# irf540_V2_0.net
KiCad netlist of a schematic drawn in Altium Designer
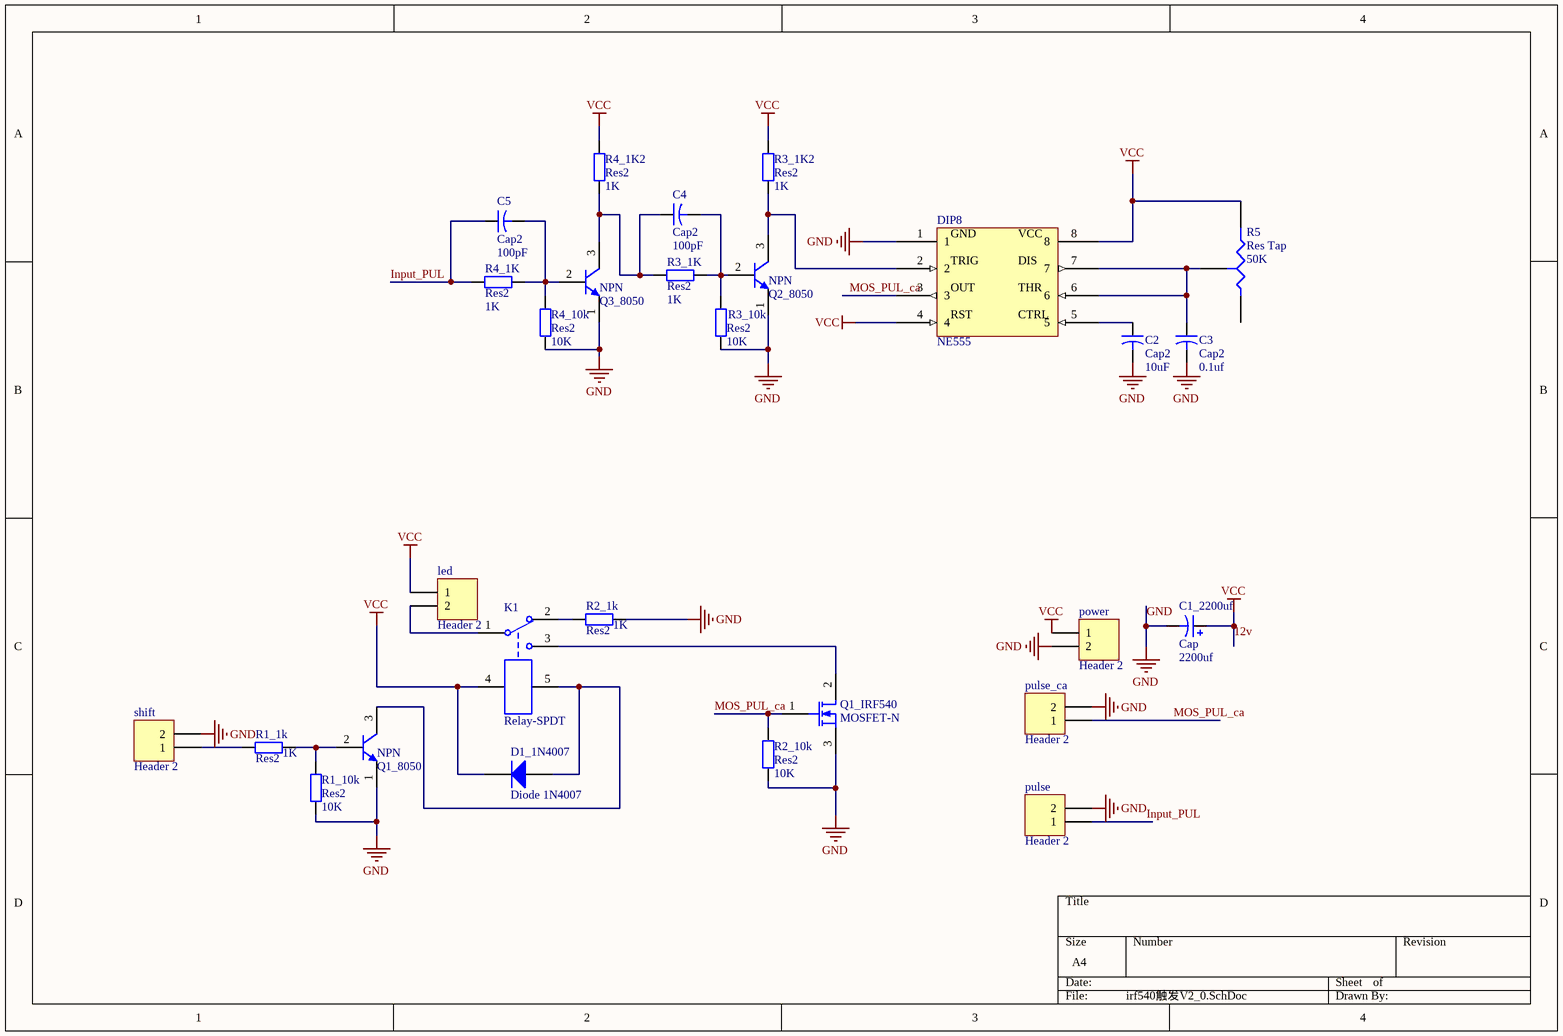
[diagram p0: irf540触发V2_0.SchDoc]

(export (version "E")
  (design (tool "Eeschema 10.0.6"))
  (components
    (comp (ref "C1_2200uf")
      (value "Cap")
      (footprint "RB7.6-15")
      (description "Polarized Capacitor (Radial)")
      (fields (field (name "ALTIUM_VALUE") "2200uf") (field (name "PUBLISHER") "Altium Limited"))
      (libsource (lib "Miscellaneous Devices") (part "Cap Pol1"))
    )
    (comp (ref "C2")
      (value "Cap2")
      (footprint "CAPR5-4X5")
      (description "Capacitor")
      (fields (field (name "ALTIUM_VALUE") "10uF") (field (name "PUBLISHER") "Altium Limited"))
      (libsource (lib "Miscellaneous Devices") (part "Cap2"))
    )
    (comp (ref "C3")
      (value "Cap2")
      (footprint "CAPR5-4X5")
      (description "Capacitor")
      (fields (field (name "ALTIUM_VALUE") "0.1uf") (field (name "PUBLISHER") "Altium Limited"))
      (libsource (lib "Miscellaneous Devices") (part "Cap2"))
    )
    (comp (ref "C4")
      (value "Cap2")
      (footprint "CAPR5-4X5")
      (description "Capacitor")
      (fields (field (name "ALTIUM_VALUE") "100pF") (field (name "PUBLISHER") "Altium Limited"))
      (libsource (lib "Miscellaneous Devices") (part "Cap2"))
    )
    (comp (ref "C5")
      (value "Cap2")
      (footprint "CAPR5-4X5")
      (description "Capacitor")
      (fields (field (name "ALTIUM_VALUE") "100pF") (field (name "PUBLISHER") "Altium Limited"))
      (libsource (lib "Miscellaneous Devices") (part "Cap2"))
    )
    (comp (ref "D1_1N4007")
      (value "Diode 1N4007")
      (footprint "DO-41")
      (description "1 Amp General Purpose Rectifier")
      (fields (field (name "PUBLISHER") "Altium Limited"))
      (libsource (lib "Miscellaneous Devices") (part "Diode 1N4007"))
    )
    (comp (ref "DIP8") (value "NE555") (footprint "DIP8") (libsource (lib "NE555") (part "NE555")))
    (comp (ref "K1")
      (value "Relay-SPDT")
      (footprint "RELAY_SDR")
      (description "Single-Pole Dual-Throw Relay")
      (fields (field (name "PUBLISHER") "Altium Limited"))
      (libsource (lib "Miscellaneous Devices") (part "Relay-SPDT"))
    )
    (comp (ref "led")
      (value "Header 2")
      (footprint "HDR1X2")
      (description "Header, 2-Pin")
      (fields (field (name "PUBLISHER") "Altium Limited"))
      (libsource (lib "") (part "Header 2_1"))
    )
    (comp (ref "power")
      (value "Header 2")
      (footprint "HDR1X2")
      (description "Header, 2-Pin")
      (fields (field (name "PUBLISHER") "Altium Limited"))
      (libsource (lib "") (part "Header 2_1"))
    )
    (comp (ref "pulse")
      (value "Header 2")
      (footprint "HDR1X2")
      (description "Header, 2-Pin")
      (fields (field (name "PUBLISHER") "Altium Limited"))
      (libsource (lib "Miscellaneous Connectors") (part "Header 2"))
    )
    (comp (ref "pulse_ca")
      (value "Header 2")
      (footprint "HDR1X2")
      (description "Header, 2-Pin")
      (fields (field (name "PUBLISHER") "Altium Limited"))
      (libsource (lib "Miscellaneous Connectors") (part "Header 2"))
    )
    (comp (ref "Q1_8050")
      (value "NPN")
      (footprint "TO-226-AA")
      (description "NPN Bipolar Transistor")
      (fields (field (name "PUBLISHER") "Altium Limited"))
      (libsource (lib "Miscellaneous Devices") (part "NPN"))
    )
    (comp (ref "Q1_IRF540")
      (value "MOSFET-N")
      (footprint "PCBComponent_1")
      (description "N-Channel MOSFET")
      (fields (field (name "PUBLISHER") "Altium Limited"))
      (libsource (lib "Miscellaneous Devices") (part "MOSFET-N"))
    )
    (comp (ref "Q2_8050")
      (value "NPN")
      (footprint "TO-226-AA")
      (description "NPN Bipolar Transistor")
      (fields (field (name "PUBLISHER") "Altium Limited"))
      (libsource (lib "Miscellaneous Devices") (part "NPN"))
    )
    (comp (ref "Q3_8050")
      (value "NPN")
      (footprint "TO-226-AA")
      (description "NPN Bipolar Transistor")
      (fields (field (name "PUBLISHER") "Altium Limited"))
      (libsource (lib "Miscellaneous Devices") (part "NPN"))
    )
    (comp (ref "R1_1k")
      (value "Res2")
      (footprint "AXIAL-0.4")
      (description "Resistor")
      (fields (field (name "ALTIUM_VALUE") "1K") (field (name "PUBLISHER") "Altium Limited"))
      (libsource (lib "") (part "Res2_3"))
    )
    (comp (ref "R1_10k")
      (value "Res2")
      (footprint "AXIAL-0.4")
      (description "Resistor")
      (fields (field (name "ALTIUM_VALUE") "10K") (field (name "PUBLISHER") "Altium Limited"))
      (libsource (lib "") (part "Res2_1"))
    )
    (comp (ref "R2_1k")
      (value "Res2")
      (footprint "AXIAL-0.4")
      (description "Resistor")
      (fields (field (name "ALTIUM_VALUE") "1K") (field (name "PUBLISHER") "Altium Limited"))
      (libsource (lib "") (part "Res2_3"))
    )
    (comp (ref "R2_10k")
      (value "Res2")
      (footprint "AXIAL-0.4")
      (description "Resistor")
      (fields (field (name "ALTIUM_VALUE") "10K") (field (name "PUBLISHER") "Altium Limited"))
      (libsource (lib "") (part "Res2_1"))
    )
    (comp (ref "R3_1K")
      (value "Res2")
      (footprint "AXIAL-0.4")
      (description "Resistor")
      (fields (field (name "ALTIUM_VALUE") "1K") (field (name "PUBLISHER") "Altium Limited"))
      (libsource (lib "Miscellaneous Devices") (part "Res2"))
    )
    (comp (ref "R3_1K2")
      (value "Res2")
      (footprint "AXIAL-0.4")
      (description "Resistor")
      (fields (field (name "ALTIUM_VALUE") "1K") (field (name "PUBLISHER") "Altium Limited"))
      (libsource (lib "") (part "Res2_2"))
    )
    (comp (ref "R3_10k")
      (value "Res2")
      (footprint "AXIAL-0.4")
      (description "Resistor")
      (fields (field (name "ALTIUM_VALUE") "10K") (field (name "PUBLISHER") "Altium Limited"))
      (libsource (lib "") (part "Res2_1"))
    )
    (comp (ref "R4_1K")
      (value "Res2")
      (footprint "AXIAL-0.4")
      (description "Resistor")
      (fields (field (name "ALTIUM_VALUE") "1K") (field (name "PUBLISHER") "Altium Limited"))
      (libsource (lib "Miscellaneous Devices") (part "Res2"))
    )
    (comp (ref "R4_1K2")
      (value "Res2")
      (footprint "AXIAL-0.4")
      (description "Resistor")
      (fields (field (name "ALTIUM_VALUE") "1K") (field (name "PUBLISHER") "Altium Limited"))
      (libsource (lib "") (part "Res2_2"))
    )
    (comp (ref "R4_10k")
      (value "Res2")
      (footprint "AXIAL-0.4")
      (description "Resistor")
      (fields (field (name "ALTIUM_VALUE") "10K") (field (name "PUBLISHER") "Altium Limited"))
      (libsource (lib "") (part "Res2_1"))
    )
    (comp (ref "R5")
      (value "Res Tap")
      (footprint "VR5")
      (description "Tapped Resistor")
      (fields (field (name "ALTIUM_VALUE") "50K") (field (name "PUBLISHER") "Altium Limited"))
      (libsource (lib "Miscellaneous Devices") (part "Res Tap"))
    )
    (comp (ref "shift")
      (value "Header 2")
      (footprint "HDR1X2")
      (description "Header, 2-Pin")
      (fields (field (name "PUBLISHER") "Altium Limited"))
      (libsource (lib "Miscellaneous Connectors") (part "Header 2"))
    )
  )
  (nets
    (net (code "1") (name "/Input_PUL") (class "Default")
      (node (ref "C5") (pin "1") (pinfunction "1_1") (pintype "passive"))
      (node (ref "R4_1K") (pin "2") (pinfunction "2_2") (pintype "passive"))
      (node (ref "pulse") (pin "1") (pinfunction "1_1") (pintype "passive"))
    )
    (net (code "2") (name "/MOS_PUL_ca") (class "Default")
      (node (ref "DIP8") (pin "3") (pinfunction "3_3") (pintype "output"))
      (node (ref "Q1_IRF540") (pin "1") (pinfunction "G_1") (pintype "passive"))
      (node (ref "R2_10k") (pin "2") (pinfunction "2_2") (pintype "passive"))
      (node (ref "pulse_ca") (pin "1") (pinfunction "1_1") (pintype "passive"))
    )
    (net (code "3") (name "GND") (class "Default")
      (node (ref "C1_2200uf") (pin "2") (pinfunction "2_2") (pintype "passive"))
      (node (ref "C2") (pin "2") (pinfunction "2_2") (pintype "passive"))
      (node (ref "C3") (pin "2") (pinfunction "2_2") (pintype "passive"))
      (node (ref "DIP8") (pin "1") (pinfunction "1_1") (pintype "passive"))
      (node (ref "Q1_8050") (pin "1") (pinfunction "E_1") (pintype "passive"))
      (node (ref "Q1_IRF540") (pin "3") (pinfunction "S_3") (pintype "passive"))
      (node (ref "Q2_8050") (pin "1") (pinfunction "E_1") (pintype "passive"))
      (node (ref "Q3_8050") (pin "1") (pinfunction "E_1") (pintype "passive"))
      (node (ref "R1_10k") (pin "1") (pinfunction "1_1") (pintype "passive"))
      (node (ref "R2_10k") (pin "1") (pinfunction "1_1") (pintype "passive"))
      (node (ref "R2_1k") (pin "2") (pinfunction "2_2") (pintype "passive"))
      (node (ref "R3_10k") (pin "1") (pinfunction "1_1") (pintype "passive"))
      (node (ref "R4_10k") (pin "1") (pinfunction "1_1") (pintype "passive"))
      (node (ref "power") (pin "2") (pinfunction "2_2") (pintype "passive"))
      (node (ref "pulse") (pin "2") (pinfunction "2_2") (pintype "passive"))
      (node (ref "pulse_ca") (pin "2") (pinfunction "2_2") (pintype "passive"))
      (node (ref "shift") (pin "2") (pinfunction "2_2") (pintype "passive"))
    )
    (net (code "4") (name "Net-(C2-Pad1)") (class "Default")
      (node (ref "C2") (pin "1") (pinfunction "1_1") (pintype "passive"))
      (node (ref "DIP8") (pin "5") (pinfunction "5_5") (pintype "input"))
    )
    (net (code "5") (name "Net-(D1_1N4007-A)") (class "Default")
      (node (ref "D1_1N4007") (pin "1") (pinfunction "A_1") (pintype "passive"))
      (node (ref "K1") (pin "5") (pinfunction "5_5") (pintype "passive"))
      (node (ref "Q1_8050") (pin "3") (pinfunction "C_3") (pintype "passive"))
    )
    (net (code "6") (name "Net-(K1-Pad1)") (class "Default")
      (node (ref "K1") (pin "1") (pinfunction "1_1") (pintype "passive"))
      (node (ref "led") (pin "2") (pinfunction "2_2") (pintype "passive"))
    )
    (net (code "7") (name "Net-(K1-Pad2)") (class "Default")
      (node (ref "K1") (pin "2") (pinfunction "2_2") (pintype "passive"))
      (node (ref "R2_1k") (pin "1") (pinfunction "1_1") (pintype "passive"))
    )
    (net (code "8") (name "Net-(Q1_8050-B)") (class "Default")
      (node (ref "Q1_8050") (pin "2") (pinfunction "B_2") (pintype "passive"))
      (node (ref "R1_10k") (pin "2") (pinfunction "2_2") (pintype "passive"))
      (node (ref "R1_1k") (pin "2") (pinfunction "2_2") (pintype "passive"))
    )
    (net (code "9") (name "Net-(Q1_IRF540-D)") (class "Default")
      (node (ref "K1") (pin "3") (pinfunction "3_3") (pintype "passive"))
      (node (ref "Q1_IRF540") (pin "2") (pinfunction "D_2") (pintype "passive"))
    )
    (net (code "10") (name "Net-(Q2_8050-B)") (class "Default")
      (node (ref "C4") (pin "2") (pinfunction "2_2") (pintype "passive"))
      (node (ref "Q2_8050") (pin "2") (pinfunction "B_2") (pintype "passive"))
      (node (ref "R3_10k") (pin "2") (pinfunction "2_2") (pintype "passive"))
      (node (ref "R3_1K") (pin "1") (pinfunction "1_1") (pintype "passive"))
    )
    (net (code "11") (name "Net-(Q2_8050-C)") (class "Default")
      (node (ref "DIP8") (pin "2") (pinfunction "2_2") (pintype "input"))
      (node (ref "Q2_8050") (pin "3") (pinfunction "C_3") (pintype "passive"))
      (node (ref "R3_1K2") (pin "2") (pinfunction "2_2") (pintype "passive"))
    )
    (net (code "12") (name "Net-(Q3_8050-B)") (class "Default")
      (node (ref "C5") (pin "2") (pinfunction "2_2") (pintype "passive"))
      (node (ref "Q3_8050") (pin "2") (pinfunction "B_2") (pintype "passive"))
      (node (ref "R4_10k") (pin "2") (pinfunction "2_2") (pintype "passive"))
      (node (ref "R4_1K") (pin "1") (pinfunction "1_1") (pintype "passive"))
    )
    (net (code "13") (name "Net-(Q3_8050-C)") (class "Default")
      (node (ref "C4") (pin "1") (pinfunction "1_1") (pintype "passive"))
      (node (ref "Q3_8050") (pin "3") (pinfunction "C_3") (pintype "passive"))
      (node (ref "R3_1K") (pin "2") (pinfunction "2_2") (pintype "passive"))
      (node (ref "R4_1K2") (pin "2") (pinfunction "2_2") (pintype "passive"))
    )
    (net (code "14") (name "Net-(R1_1k-Pad1)") (class "Default")
      (node (ref "R1_1k") (pin "1") (pinfunction "1_1") (pintype "passive"))
      (node (ref "shift") (pin "1") (pinfunction "1_1") (pintype "passive"))
    )
    (net (code "15") (name "Net-(R5-TAP)") (class "Default")
      (node (ref "C3") (pin "1") (pinfunction "1_1") (pintype "passive"))
      (node (ref "DIP8") (pin "6") (pinfunction "6_6") (pintype "input"))
      (node (ref "DIP8") (pin "7") (pinfunction "7_7") (pintype "output"))
      (node (ref "R5") (pin "3") (pinfunction "TAP_3") (pintype "passive"))
    )
    (net (code "16") (name "VCC") (class "Default")
      (node (ref "C1_2200uf") (pin "1") (pinfunction "1_1") (pintype "passive"))
      (node (ref "D1_1N4007") (pin "2") (pinfunction "K_2") (pintype "passive"))
      (node (ref "DIP8") (pin "4") (pinfunction "4_4") (pintype "input"))
      (node (ref "DIP8") (pin "8") (pinfunction "8_8") (pintype "passive"))
      (node (ref "K1") (pin "4") (pinfunction "4_4") (pintype "passive"))
      (node (ref "R3_1K2") (pin "1") (pinfunction "1_1") (pintype "passive"))
      (node (ref "R4_1K2") (pin "1") (pinfunction "1_1") (pintype "passive"))
      (node (ref "R5") (pin "2") (pinfunction "B_2") (pintype "passive"))
      (node (ref "led") (pin "1") (pinfunction "1_1") (pintype "passive"))
      (node (ref "power") (pin "1") (pinfunction "1_1") (pintype "passive"))
    )
    (net (code "17") (name "unconnected-(R5-A-Pad1)") (class "Default")
      (node (ref "R5") (pin "1") (pinfunction "A_1") (pintype "passive"))
    )
  )
)
